# passive_LPF.net
KiCad netlist of a schematic drawn in EAGLE
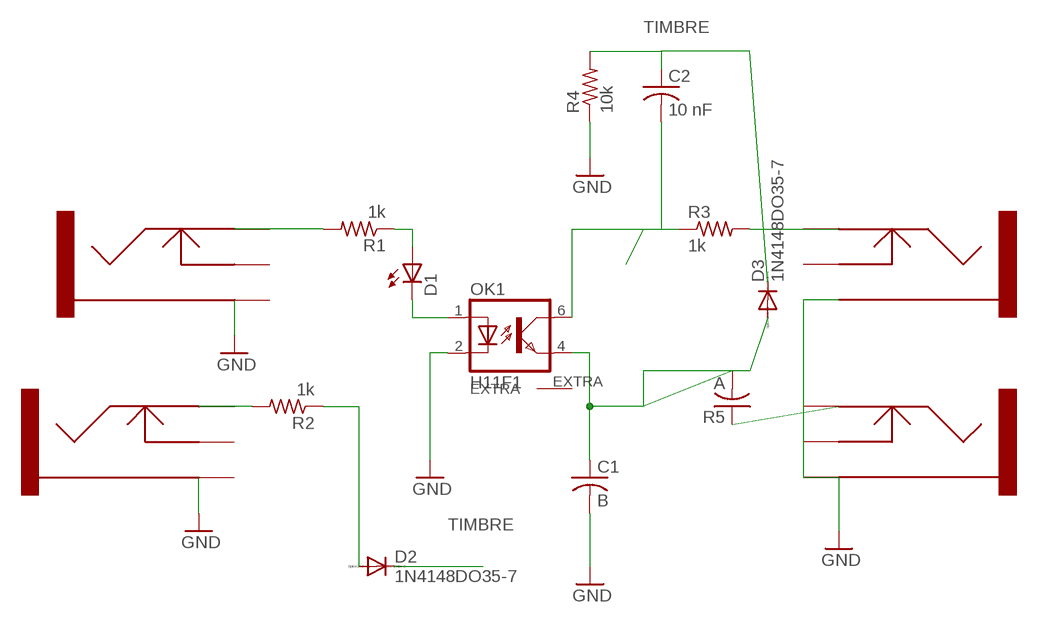
[diagram p0: schematic, sheet 1]

(export (version "E")
  (design (tool "Eeschema 10.0.6"))
  (components
    (comp (ref "C1")
      (value "B")
      (footprint "eagle-import:C050-025X075")
      (libsource (lib "eagle-import") (part "C-US050-025X075"))
    )
    (comp (ref "C2")
      (value "10 nF")
      (footprint "eagle-import:C025-024X044")
      (libsource (lib "eagle-import") (part "rcl_C-US025-024X044"))
    )
    (comp (ref "CV1")
      (value "3.5MMJACK")
      (footprint "eagle-import:3.5MMPHONEJACK")
      (libsource (lib "eagle-import") (part "3.5MMJACK"))
    )
    (comp (ref "CV2")
      (value "3.5MMJACK")
      (footprint "eagle-import:3.5MMPHONEJACK")
      (libsource (lib "eagle-import") (part "3.5MMJACK"))
    )
    (comp (ref "D1")
      (value "LED3MM")
      (footprint "eagle-import:LED3MM")
      (libsource (lib "eagle-import") (part "LED3MM"))
    )
    (comp (ref "D2")
      (value "1N4148DO35-7")
      (footprint "eagle-import:DO35-7")
      (libsource (lib "eagle-import") (part "1N4148DO35-7"))
    )
    (comp (ref "D3")
      (value "1N4148DO35-7")
      (footprint "eagle-import:DO35-7")
      (libsource (lib "eagle-import") (part "1N4148DO35-7"))
    )
    (comp (ref "IN")
      (value "3.5MMJACK")
      (footprint "eagle-import:3.5MMPHONEJACK")
      (libsource (lib "eagle-import") (part "3.5MMJACK"))
    )
    (comp (ref "OK1")
      (value "H11F1")
      (footprint "eagle-import:DIL05")
      (libsource (lib "eagle-import") (part "H11F1"))
    )
    (comp (ref "OUT")
      (value "3.5MMJACK")
      (footprint "eagle-import:3.5MMPHONEJACK")
      (libsource (lib "eagle-import") (part "3.5MMJACK"))
    )
    (comp (ref "R1")
      (value "1k")
      (footprint "eagle-import:0207_2V")
      (libsource (lib "eagle-import") (part "R-US_0207/2V"))
    )
    (comp (ref "R2")
      (value "1k")
      (footprint "eagle-import:0207_2V")
      (libsource (lib "eagle-import") (part "R-US_0207/2V"))
    )
    (comp (ref "R3")
      (value "1k")
      (footprint "eagle-import:0207_2V")
      (libsource (lib "eagle-import") (part "R-US_0207/2V"))
    )
    (comp (ref "R4")
      (value "10k")
      (footprint "eagle-import:0207_2V")
      (libsource (lib "eagle-import") (part "R-US_0207/2V"))
    )
    (comp (ref "R5")
      (value "A")
      (footprint "eagle-import:C050-025X075")
      (libsource (lib "eagle-import") (part "C-US050-025X075"))
    )
  )
  (nets
    (net (code "1") (name "/TIMBRE") (class "Default")
      (node (ref "C2") (pin "1") (pinfunction "1_1") (pintype "passive"))
      (node (ref "D2") (pin "C") (pinfunction "C_C") (pintype "passive"))
      (node (ref "D3") (pin "C") (pinfunction "C_C") (pintype "passive"))
      (node (ref "R4") (pin "2") (pinfunction "2_2") (pintype "passive"))
    )
    (net (code "2") (name "GND") (class "Default")
      (node (ref "C1") (pin "2") (pinfunction "2_2") (pintype "passive"))
      (node (ref "CV1") (pin "SLEEVE") (pinfunction "SLEEVE_SLEEVE") (pintype "bidirectional"))
      (node (ref "CV2") (pin "SLEEVE") (pinfunction "SLEEVE_SLEEVE") (pintype "bidirectional"))
      (node (ref "IN") (pin "SLEEVE") (pinfunction "SLEEVE_SLEEVE") (pintype "bidirectional"))
      (node (ref "OK1") (pin "2") (pinfunction "C_2") (pintype "passive"))
      (node (ref "OUT") (pin "SLEEVE") (pinfunction "SLEEVE_SLEEVE") (pintype "bidirectional"))
      (node (ref "R4") (pin "1") (pinfunction "1_1") (pintype "passive"))
    )
    (net (code "3") (name "Net-(CV1-PadTIP)") (class "Default")
      (node (ref "CV1") (pin "TIP") (pinfunction "TIP_TIP") (pintype "bidirectional"))
      (node (ref "R2") (pin "2") (pinfunction "2_2") (pintype "passive"))
    )
    (net (code "4") (name "Net-(CV2-PadTIP)") (class "Default")
      (node (ref "CV2") (pin "TIP") (pinfunction "TIP_TIP") (pintype "bidirectional"))
      (node (ref "R1") (pin "2") (pinfunction "2_2") (pintype "passive"))
    )
    (net (code "5") (name "Net-(D1-C)") (class "Default")
      (node (ref "D1") (pin "K") (pinfunction "C_K") (pintype "passive"))
      (node (ref "OK1") (pin "1") (pinfunction "A_1") (pintype "passive"))
    )
    (net (code "6") (name "Net-(D1-PadA)") (class "Default")
      (node (ref "D1") (pin "A") (pinfunction "A_A") (pintype "passive"))
      (node (ref "R1") (pin "1") (pinfunction "1_1") (pintype "passive"))
    )
    (net (code "7") (name "Net-(D2-PadA)") (class "Default")
      (node (ref "D2") (pin "A") (pinfunction "A_A") (pintype "passive"))
      (node (ref "R2") (pin "1") (pinfunction "1_1") (pintype "passive"))
    )
    (net (code "8") (name "Net-(IN-PadTIP)") (class "Default")
      (node (ref "IN") (pin "TIP") (pinfunction "TIP_TIP") (pintype "bidirectional"))
      (node (ref "R5") (pin "1") (pinfunction "1_1") (pintype "passive"))
    )
    (net (code "9") (name "Net-(OK1-COL)") (class "Default")
      (node (ref "C2") (pin "2") (pinfunction "2_2") (pintype "passive"))
      (node (ref "OK1") (pin "6") (pinfunction "COL_6") (pintype "passive"))
      (node (ref "R3") (pin "1") (pinfunction "1_1") (pintype "passive"))
    )
    (net (code "10") (name "Net-(OK1-EMIT)") (class "Default")
      (node (ref "C1") (pin "1") (pinfunction "1_1") (pintype "passive"))
      (node (ref "D3") (pin "A") (pinfunction "A_A") (pintype "passive"))
      (node (ref "OK1") (pin "4") (pinfunction "EMIT_4") (pintype "passive"))
      (node (ref "R5") (pin "2") (pinfunction "2_2") (pintype "passive"))
    )
    (net (code "11") (name "Net-(OUT-PadTIP)") (class "Default")
      (node (ref "OUT") (pin "TIP") (pinfunction "TIP_TIP") (pintype "bidirectional"))
      (node (ref "R3") (pin "2") (pinfunction "2_2") (pintype "passive"))
    )
    (net (code "12") (name "unconnected-(CV1-PadSWITCH)") (class "Default")
      (node (ref "CV1") (pin "SWITCH") (pinfunction "SWITCH_SWITCH") (pintype "bidirectional"))
    )
    (net (code "13") (name "unconnected-(CV2-PadSWITCH)") (class "Default")
      (node (ref "CV2") (pin "SWITCH") (pinfunction "SWITCH_SWITCH") (pintype "bidirectional"))
    )
    (net (code "14") (name "unconnected-(IN-PadSWITCH)") (class "Default")
      (node (ref "IN") (pin "SWITCH") (pinfunction "SWITCH_SWITCH") (pintype "bidirectional"))
    )
    (net (code "15") (name "unconnected-(OK1-PadEXTRA)") (class "Default")
      (node (ref "OK1") (pin "EXTRA") (pinfunction "EXTRA_EXTRA") (pintype "bidirectional"))
    )
    (net (code "16") (name "unconnected-(OUT-PadSWITCH)") (class "Default")
      (node (ref "OUT") (pin "SWITCH") (pinfunction "SWITCH_SWITCH") (pintype "bidirectional"))
    )
  )
)
